# Connector-Section.net
KiCad netlist of a schematic drawn in Altium Designer
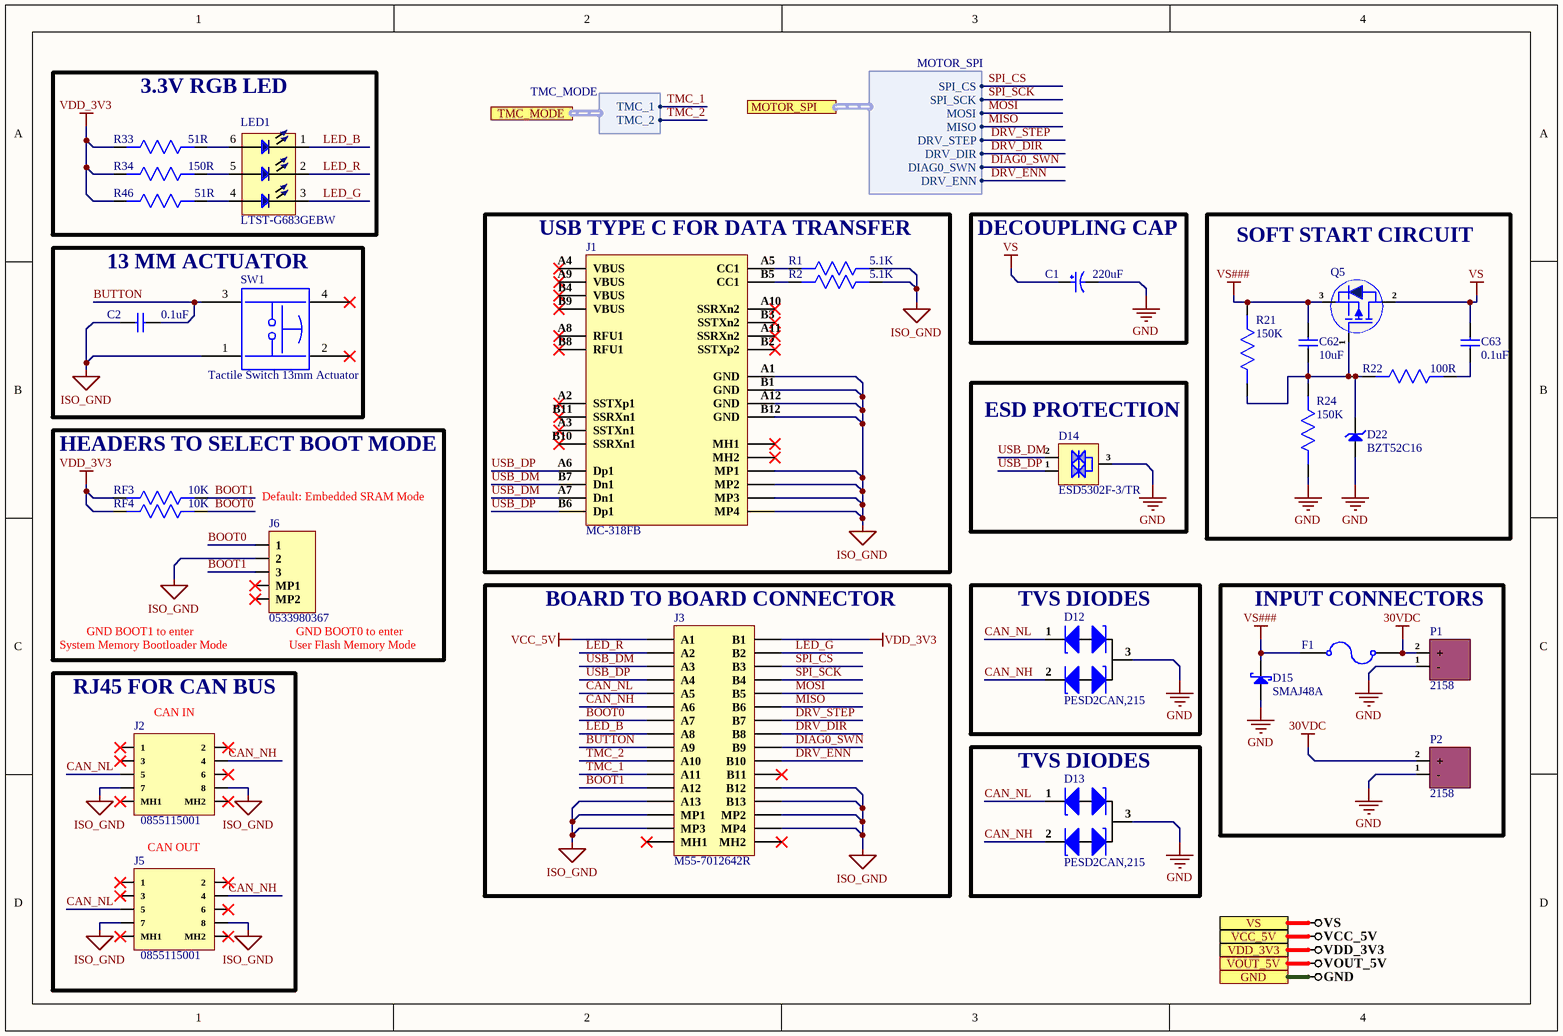
[diagram p0: Connector-Section.SchDoc]

(export (version "E")
  (design (tool "Eeschema 10.0.6"))
  (components
    (comp (ref "C1")
      (value "220uF")
      (footprint "EEEFT1H221AP")
      (description "CAP ALUM 220UF 20% 50V SMD")
      (fields
        (field (name "MANUFACTURER") "Panasonic")
        (field (name "MANUFACTURER PART NUMBER") "EEEFT1H221AP")
      )
      (libsource (lib "eSpark_centralized_Library(2022)") (part "EEEFT1H221AP"))
    )
    (comp (ref "C2")
      (value "0.1uF")
      (footprint "Cap 0603")
      (description "Cap Ceramic 0.1uF 50VDC X7R 10% SMD 0603 Paper T/R")
      (fields
        (field (name "MANUFACTURER") "Samsung")
        (field (name "MANUFACTURER PART NUMBER") "CL10B104KB8NNNC")
      )
      (libsource (lib "Cole_Benson") (part "CL10B104KB8NNNC"))
    )
    (comp (ref "C62")
      (value "10uF")
      (footprint "Cap 0603")
      (description "10uF 35V X5R 20% Pad SMD 0603")
      (fields
        (field (name "MANUFACTURER") "Murata")
        (field (name "MANUFACTURER PART NUMBER") "GRM188R6YA106MA73D")
      )
      (libsource (lib "Cole_Benson") (part "GRM188R6YA106MA73D"))
    )
    (comp (ref "C63")
      (value "0.1uF")
      (footprint "Cap 0603")
      (description "Cap Ceramic 0.1uF 50VDC X7R 10% SMD 0603 Paper T/R")
      (fields
        (field (name "MANUFACTURER") "Samsung")
        (field (name "MANUFACTURER PART NUMBER") "CL10B104KB8NNNC")
      )
      (libsource (lib "Cole_Benson") (part "CL10B104KB8NNNC"))
    )
    (comp (ref "D12")
      (value "PESD2CAN,215")
      (footprint "SOT-23")
      (description "TVS DIODE 24VWM 41VC TO236AB")
      (fields (field (name "MANUFACTURER") "Nexperia"))
      (libsource (lib "Cole_Benson") (part "PESD2CAN,215"))
    )
    (comp (ref "D13")
      (value "PESD2CAN,215")
      (footprint "SOT-23")
      (description "TVS DIODE 24VWM 41VC TO236AB")
      (fields (field (name "MANUFACTURER") "Nexperia"))
      (libsource (lib "Cole_Benson") (part "PESD2CAN,215"))
    )
    (comp (ref "D14")
      (value "ESD5302F-3/TR")
      (footprint "Sot-23")
      (description "16A 20V 7V 5V@Max Unidirectional SOT-23 TVS ROHS")
      (fields (field (name "MANUFACTURER") "WILLSEMI") (field (name "LCSC PART NUMBER") "C239643"))
      (libsource (lib "eSpark Libraries") (part "ESD5302F-3/TR"))
    )
    (comp (ref "D15")
      (value "SMAJ48A")
      (footprint "SMA")
      (description "TVS DIODE 48VWM 77.4VC DO214AC")
      (fields (field (name "MANUFACTURER") "Littelfuse") (field (name "LCSC PART NUMBER") "C223991"))
      (libsource (lib "Cole_Benson") (part "SMAJ48A"))
    )
    (comp (ref "D22")
      (value "BZT52C16")
      (footprint "SOD-123")
      (description "±5% Single 15.3V~17.1V 500mW 16V SOD-123 Zener Diodes ROHS")
      (fields (field (name "MANUFACTURER") "Shikues") (field (name "LCSC PART NUMBER") "C216724"))
      (libsource (lib "Cole_Benson") (part "BZT52C16"))
    )
    (comp (ref "F1")
      (value "0685H9150-01")
      (footprint "0685H9150-01")
      (description "FUSE BOARD MNT 15A 125VAC 32VDC")
      (fields (field (name "MANUFACTURER") "Bel"))
      (libsource (lib "Cole_Benson") (part "0685H9150-01"))
    )
    (comp (ref "J1")
      (value "MC-318FB")
      (footprint "MC-318FB")
      (description "USB 3.0 3A 1 Brick nogging 24 Female -35℃~+75℃ Type-C SMD USB Connectors ROHS")
      (fields (field (name "MANUFACTURER") "SOFNG"))
      (libsource (lib "Cole_Benson") (part "MC-318FB"))
    )
    (comp (ref "J2")
      (value "0855115001")
      (footprint "0855115001")
      (description "CONN MOD JACK 8P8C VERT UNSHLD")
      (fields (field (name "MANUFACTURER") "Molex") (field (name "MANUFACTURER PART NUMBER") "85511-5001"))
      (libsource (lib "eSpark_centralized_Library(2022)") (part "0855115001"))
    )
    (comp (ref "J3")
      (value "M55-7012642R")
      (footprint "M55-7012642R")
      (description "CONN HEADER SMD 26POS 1.27MM")
      (fields (field (name "MANUFACTURER") "Harwin"))
      (libsource (lib "Cole_Benson") (part "M55-7012642R"))
    )
    (comp (ref "J5")
      (value "0855115001")
      (footprint "0855115001")
      (description "CONN MOD JACK 8P8C VERT UNSHLD")
      (fields (field (name "MANUFACTURER") "Molex") (field (name "MANUFACTURER PART NUMBER") "85511-5001"))
      (libsource (lib "eSpark_centralized_Library(2022)") (part "0855115001"))
    )
    (comp (ref "J6")
      (value "0533980367")
      (footprint "0533980367")
      (description "CONN HEADER SMD 3POS 1.25MM")
      (fields (field (name "MANUFACTURER") "Molex"))
      (libsource (lib "Cole_Benson") (part "0533980367"))
    )
    (comp (ref "LED1")
      (value "LTST-G683GEBW")
      (footprint "LTST-G683GEBW")
      (description "Standard LEDs - SMD SMD LED Red/Grn/Blue 625/1550/260 mcd")
      (fields (field (name "MANUFACTURER") "Vishay Lite-On"))
      (libsource (lib "Cole_Benson") (part "LTST-G683GEBW"))
    )
    (comp (ref "P1")
      (value "2158")
      (footprint "2158")
      (description "XT60 Connector Male-Female Pair, Black (Pololu)")
      (fields (field (name "MANUFACTURER") "Polulo"))
      (libsource (lib "Cole_Benson") (part "2158"))
    )
    (comp (ref "P2")
      (value "2158")
      (footprint "2158")
      (description "XT60 Connector Male-Female Pair, Black (Pololu)")
      (fields (field (name "MANUFACTURER") "Polulo"))
      (libsource (lib "Cole_Benson") (part "2158"))
    )
    (comp (ref "Q5")
      (value "STD10P6F6")
      (footprint "DPAK")
      (description "MOSFET P CH 60V 10A DPAK")
      (fields (field (name "MANUFACTURER") "STMicroelectronics") (field (name "LCSC PART NUMBER") "C457501"))
      (libsource (lib "Cole_Benson") (part "STD10P6F6"))
    )
    (comp (ref "R1")
      (value "5.1K")
      (footprint "Res0603")
      (description "RES SMD 5.1K OHM 5% 1/10W 0603")
      (fields
        (field (name "MANUFACTURER") "Yageo")
        (field (name "MANUFACTURER PART NUMBER") "RC0603JR-075K1L")
      )
      (libsource (lib "Cole_Benson") (part "RC0603JR-075K1L"))
    )
    (comp (ref "R2")
      (value "5.1K")
      (footprint "Res0603")
      (description "RES SMD 5.1K OHM 5% 1/10W 0603")
      (fields
        (field (name "MANUFACTURER") "Yageo")
        (field (name "MANUFACTURER PART NUMBER") "RC0603JR-075K1L")
      )
      (libsource (lib "Cole_Benson") (part "RC0603JR-075K1L"))
    )
    (comp (ref "R21")
      (value "150K")
      (footprint "Res0603")
      (description "RES SMD 150K OHM 5% 1/10W 0603")
      (fields
        (field (name "MANUFACTURER") "Yageo")
        (field (name "MANUFACTURER PART NUMBER") "AC0603JR-07150KL")
      )
      (libsource (lib "Cole_Benson") (part "AC0603JR-07150KL"))
    )
    (comp (ref "R22")
      (value "100R")
      (footprint "Res0603")
      (description "RES SMD 100 OHM 1% 1/10W 0603")
      (fields
        (field (name "MANUFACTURER") "Yageo")
        (field (name "MANUFACTURER PART NUMBER") "RC0603FR-07100RL")
      )
      (libsource (lib "Cole_Benson") (part "RC0603FR-07100RL"))
    )
    (comp (ref "R24")
      (value "150K")
      (footprint "Res0603")
      (description "RES SMD 150K OHM 5% 1/10W 0603")
      (fields
        (field (name "MANUFACTURER") "Yageo")
        (field (name "MANUFACTURER PART NUMBER") "AC0603JR-07150KL")
      )
      (libsource (lib "Cole_Benson") (part "AC0603JR-07150KL"))
    )
    (comp (ref "R33")
      (value "51R")
      (footprint "Res0603")
      (description "RES SMD 51R 100mW 0603")
      (fields
        (field (name "MANUFACTURER") "Yageo")
        (field (name "MANUFACTURER PART NUMBER") "RC0603FR-0751RL")
      )
      (libsource (lib "Cole_Benson") (part "RC0603FR-0751RL"))
    )
    (comp (ref "R34")
      (value "150R")
      (footprint "Res0603")
      (description "RES SMD 150OHM 1/10W 0603")
      (fields
        (field (name "MANUFACTURER") "Yageo")
        (field (name "MANUFACTURER PART NUMBER") "RC0603FR-07150RL")
      )
      (libsource (lib "Cole_Benson") (part "RC0603FR-07150RL"))
    )
    (comp (ref "R46")
      (value "51R")
      (footprint "Res0603")
      (description "RES SMD 51R 100mW 0603")
      (fields
        (field (name "MANUFACTURER") "Yageo")
        (field (name "MANUFACTURER PART NUMBER") "RC0603FR-0751RL")
      )
      (libsource (lib "Cole_Benson") (part "RC0603FR-0751RL"))
    )
    (comp (ref "RF3")
      (value "10K")
      (footprint "Res0603")
      (description "RES SMD 10K Ohm 1% 1/10W 0603")
      (fields
        (field (name "MANUFACTURER") "Yageo")
        (field (name "MANUFACTURER PART NUMBER") "RC0603FR-0710KL")
      )
      (libsource (lib "Cole_Benson") (part "RC0603FR-0710KL"))
    )
    (comp (ref "RF4")
      (value "10K")
      (footprint "Res0603")
      (description "RES SMD 10K Ohm 1% 1/10W 0603")
      (fields
        (field (name "MANUFACTURER") "Yageo")
        (field (name "MANUFACTURER PART NUMBER") "RC0603FR-0710KL")
      )
      (libsource (lib "Cole_Benson") (part "RC0603FR-0710KL"))
    )
    (comp (ref "SW1")
      (value "Tactile Switch 13mm Actuator")
      (footprint "Tactile Switch 13mm Actuator")
      (description "Memontary Tactile Push Button Switch 6X6X4.3 / 4.5 / 5/6/7/8/9/10 / 13mm SMD")
      (fields
        (field (name "MANUFACTURER") "WIN ELEC-TECH CO., LTD")
        (field (name "MANUFACTURER PART NO") "Custum")
      )
      (libsource (lib "Cole_Benson") (part "Tactile Switch 13mm Actuator"))
    )
  )
  (nets
    (net (code "3") (name "/BOOT0") (class "Default")
      (node (ref "J3") (pin "A7") (pinfunction "A7_A7") (pintype "passive"))
      (node (ref "J6") (pin "1") (pinfunction "1_1") (pintype "passive"))
      (node (ref "RF4") (pin "1") (pintype "passive"))
    )
    (net (code "4") (name "/BOOT1") (class "Default")
      (node (ref "J3") (pin "A12") (pinfunction "A12_A12") (pintype "passive"))
      (node (ref "J6") (pin "3") (pinfunction "3_3") (pintype "passive"))
      (node (ref "RF3") (pin "1") (pintype "passive"))
    )
    (net (code "5") (name "/BUTTON") (class "Default")
      (node (ref "C2") (pin "2") (pinfunction "2_2") (pintype "passive"))
      (node (ref "J3") (pin "A9") (pinfunction "A9_A9") (pintype "passive"))
      (node (ref "SW1") (pin "3") (pintype "passive"))
    )
    (net (code "6") (name "/CAN_NH") (class "Default")
      (node (ref "D12") (pin "2") (pinfunction "K2_2") (pintype "passive"))
      (node (ref "D13") (pin "2") (pinfunction "K2_2") (pintype "passive"))
      (node (ref "J2") (pin "4") (pinfunction "4_4") (pintype "passive"))
      (node (ref "J3") (pin "A6") (pinfunction "A6_A6") (pintype "passive"))
      (node (ref "J5") (pin "4") (pinfunction "4_4") (pintype "passive"))
    )
    (net (code "7") (name "/CAN_NL") (class "Default")
      (node (ref "D12") (pin "1") (pinfunction "K1_1") (pintype "passive"))
      (node (ref "D13") (pin "1") (pinfunction "K1_1") (pintype "passive"))
      (node (ref "J2") (pin "5") (pinfunction "5_5") (pintype "passive"))
      (node (ref "J3") (pin "A5") (pinfunction "A5_A5") (pintype "passive"))
      (node (ref "J5") (pin "5") (pinfunction "5_5") (pintype "passive"))
    )
    (net (code "8") (name "/DIAG0_SWN") (class "Default")
      (node (ref "J3") (pin "B9") (pinfunction "B9_B9") (pintype "passive"))
    )
    (net (code "9") (name "/DRV_DIR") (class "Default")
      (node (ref "J3") (pin "B8") (pinfunction "B8_B8") (pintype "passive"))
    )
    (net (code "10") (name "/DRV_ENN") (class "Default")
      (node (ref "J3") (pin "B10") (pinfunction "B10_B10") (pintype "passive"))
    )
    (net (code "11") (name "/DRV_STEP") (class "Default")
      (node (ref "J3") (pin "B7") (pinfunction "B7_B7") (pintype "passive"))
    )
    (net (code "12") (name "/LED_B") (class "Default")
      (node (ref "J3") (pin "A8") (pinfunction "A8_A8") (pintype "passive"))
      (node (ref "LED1") (pin "1") (pinfunction "-_1") (pintype "passive"))
    )
    (net (code "13") (name "/LED_G") (class "Default")
      (node (ref "J3") (pin "B2") (pinfunction "B2_B2") (pintype "passive"))
      (node (ref "LED1") (pin "3") (pinfunction "-_3") (pintype "passive"))
    )
    (net (code "14") (name "/LED_R") (class "Default")
      (node (ref "J3") (pin "A2") (pinfunction "A2_A2") (pintype "passive"))
      (node (ref "LED1") (pin "2") (pinfunction "-_2") (pintype "passive"))
    )
    (net (code "15") (name "/MISO") (class "Default")
      (node (ref "J3") (pin "B6") (pinfunction "B6_B6") (pintype "passive"))
    )
    (net (code "16") (name "/MOSI") (class "Default")
      (node (ref "J3") (pin "B5") (pinfunction "B5_B5") (pintype "passive"))
    )
    (net (code "17") (name "/SPI_CS") (class "Default")
      (node (ref "J3") (pin "B3") (pinfunction "B3_B3") (pintype "passive"))
    )
    (net (code "18") (name "/SPI_SCK") (class "Default")
      (node (ref "J3") (pin "B4") (pinfunction "B4_B4") (pintype "passive"))
    )
    (net (code "19") (name "/TMC_1") (class "Default")
      (node (ref "J3") (pin "A11") (pinfunction "A11_A11") (pintype "passive"))
    )
    (net (code "20") (name "/TMC_2") (class "Default")
      (node (ref "J3") (pin "A10") (pinfunction "A10_A10") (pintype "passive"))
    )
    (net (code "21") (name "/USB_DM") (class "Default")
      (node (ref "D14") (pin "2") (pinfunction "I/O2_2") (pintype "passive"))
      (node (ref "J1") (pin "A7") (pinfunction "Dn1_A7") (pintype "passive"))
      (node (ref "J1") (pin "B7") (pinfunction "Dn1_B7") (pintype "passive"))
      (node (ref "J3") (pin "A3") (pinfunction "A3_A3") (pintype "passive"))
    )
    (net (code "22") (name "/USB_DP") (class "Default")
      (node (ref "D14") (pin "1") (pinfunction "I/O1_1") (pintype "passive"))
      (node (ref "J1") (pin "A6") (pinfunction "Dp1_A6") (pintype "passive"))
      (node (ref "J1") (pin "B6") (pinfunction "Dp1_B6") (pintype "passive"))
      (node (ref "J3") (pin "A4") (pinfunction "A4_A4") (pintype "passive"))
    )
    (net (code "25") (name "30VDC") (class "Default")
      (node (ref "F1") (pin "2") (pinfunction "2_2") (pintype "passive"))
      (node (ref "P1") (pin "2") (pinfunction "+_2") (pintype "passive"))
      (node (ref "P2") (pin "2") (pinfunction "+_2") (pintype "passive"))
    )
    (net (code "26") (name "GND") (class "Default")
      (node (ref "C1") (pin "2") (pintype "passive"))
      (node (ref "D12") (pin "3") (pinfunction "C_K_3") (pintype "passive"))
      (node (ref "D13") (pin "3") (pinfunction "C_K_3") (pintype "passive"))
      (node (ref "D14") (pin "3") (pinfunction "GND_3") (pintype "passive"))
      (node (ref "D15") (pin "2") (pinfunction "A_2") (pintype "passive"))
      (node (ref "D22") (pin "1") (pinfunction "A_1") (pintype "passive"))
      (node (ref "P1") (pin "1") (pinfunction "-_1") (pintype "passive"))
      (node (ref "P2") (pin "1") (pinfunction "-_1") (pintype "passive"))
      (node (ref "R24") (pin "2") (pintype "passive"))
    )
    (net (code "27") (name "ISO_GND") (class "Default")
      (node (ref "C2") (pin "1") (pinfunction "1_1") (pintype "passive"))
      (node (ref "J1") (pin "A1") (pinfunction "GND_A1") (pintype "passive"))
      (node (ref "J1") (pin "A12") (pinfunction "GND_A12") (pintype "passive"))
      (node (ref "J1") (pin "B1") (pinfunction "GND_B1") (pintype "passive"))
      (node (ref "J1") (pin "B12") (pinfunction "GND_B12") (pintype "passive"))
      (node (ref "J1") (pin "MP1") (pinfunction "MP1_MP1") (pintype "passive"))
      (node (ref "J1") (pin "MP2") (pinfunction "MP2_MP2") (pintype "passive"))
      (node (ref "J1") (pin "MP3") (pinfunction "MP3_MP3") (pintype "passive"))
      (node (ref "J1") (pin "MP4") (pinfunction "MP4_MP4") (pintype "passive"))
      (node (ref "J2") (pin "7") (pinfunction "7_7") (pintype "passive"))
      (node (ref "J2") (pin "8") (pinfunction "8_8") (pintype "passive"))
      (node (ref "J3") (pin "A13") (pinfunction "A13_A13") (pintype "passive"))
      (node (ref "J3") (pin "B12") (pinfunction "B12_B12") (pintype "passive"))
      (node (ref "J3") (pin "B13") (pinfunction "B13_B13") (pintype "passive"))
      (node (ref "J3") (pin "MP1") (pinfunction "MP1_MP1") (pintype "passive"))
      (node (ref "J3") (pin "MP2") (pinfunction "MP2_MP2") (pintype "passive"))
      (node (ref "J3") (pin "MP3") (pinfunction "MP3_MP3") (pintype "passive"))
      (node (ref "J3") (pin "MP4") (pinfunction "MP4_MP4") (pintype "passive"))
      (node (ref "J5") (pin "7") (pinfunction "7_7") (pintype "passive"))
      (node (ref "J5") (pin "8") (pinfunction "8_8") (pintype "passive"))
      (node (ref "J6") (pin "2") (pinfunction "2_2") (pintype "passive"))
      (node (ref "R1") (pin "1") (pintype "passive"))
      (node (ref "R2") (pin "1") (pintype "passive"))
      (node (ref "SW1") (pin "1") (pintype "passive"))
    )
    (net (code "28") (name "Net-(C63-Pad1)") (class "Default")
      (node (ref "C63") (pin "1") (pinfunction "1_1") (pintype "passive"))
      (node (ref "R22") (pin "1") (pintype "passive"))
    )
    (net (code "29") (name "Net-(D22-K)") (class "Default")
      (node (ref "C62") (pin "1") (pinfunction "1_1") (pintype "passive"))
      (node (ref "D22") (pin "2") (pinfunction "K_2") (pintype "passive"))
      (node (ref "Q5") (pin "1") (pinfunction "G_1") (pintype "passive"))
      (node (ref "R21") (pin "2") (pintype "passive"))
      (node (ref "R22") (pin "2") (pintype "passive"))
      (node (ref "R24") (pin "1") (pintype "passive"))
    )
    (net (code "30") (name "Net-(J1-CC1-PadA5)") (class "Default")
      (node (ref "J1") (pin "A5") (pinfunction "CC1_A5") (pintype "passive"))
      (node (ref "R1") (pin "2") (pintype "passive"))
    )
    (net (code "31") (name "Net-(J1-CC1-PadB5)") (class "Default")
      (node (ref "J1") (pin "B5") (pinfunction "CC1_B5") (pintype "passive"))
      (node (ref "R2") (pin "2") (pintype "passive"))
    )
    (net (code "32") (name "Net-(LED1-+-Pad4)") (class "Default")
      (node (ref "LED1") (pin "4") (pinfunction "+_4") (pintype "passive"))
      (node (ref "R46") (pin "1") (pintype "passive"))
    )
    (net (code "33") (name "Net-(LED1-+-Pad5)") (class "Default")
      (node (ref "LED1") (pin "5") (pinfunction "+_5") (pintype "passive"))
      (node (ref "R34") (pin "1") (pintype "passive"))
    )
    (net (code "34") (name "Net-(LED1-+-Pad6)") (class "Default")
      (node (ref "LED1") (pin "6") (pinfunction "+_6") (pintype "passive"))
      (node (ref "R33") (pin "1") (pintype "passive"))
    )
    (net (code "35") (name "VCC_5V") (class "Default")
      (node (ref "J3") (pin "A1") (pinfunction "A1_A1") (pintype "passive"))
    )
    (net (code "36") (name "VDD_3V3") (class "Default")
      (node (ref "J3") (pin "B1") (pinfunction "B1_B1") (pintype "passive"))
      (node (ref "R33") (pin "2") (pintype "passive"))
      (node (ref "R34") (pin "2") (pintype "passive"))
      (node (ref "R46") (pin "2") (pintype "passive"))
      (node (ref "RF3") (pin "2") (pintype "passive"))
      (node (ref "RF4") (pin "2") (pintype "passive"))
    )
    (net (code "38") (name "VS") (class "Default")
      (node (ref "C1") (pin "1") (pintype "passive"))
      (node (ref "C63") (pin "2") (pinfunction "2_2") (pintype "passive"))
      (node (ref "Q5") (pin "2") (pinfunction "D_2") (pintype "passive"))
    )
    (net (code "39") (name "VS###") (class "Default")
      (node (ref "C62") (pin "2") (pinfunction "2_2") (pintype "passive"))
      (node (ref "D15") (pin "1") (pinfunction "K_1") (pintype "passive"))
      (node (ref "F1") (pin "1") (pinfunction "1_1") (pintype "passive"))
      (node (ref "Q5") (pin "3") (pinfunction "S_3") (pintype "passive"))
      (node (ref "R21") (pin "1") (pintype "passive"))
    )
    (net (code "40") (name "unconnected-(J1-PadMH1)") (class "Default")
      (node (ref "J1") (pin "MH1") (pinfunction "MH1_MH1") (pintype "passive+no_connect"))
    )
    (net (code "41") (name "unconnected-(J1-PadMH2)") (class "Default")
      (node (ref "J1") (pin "MH2") (pinfunction "MH2_MH2") (pintype "passive+no_connect"))
    )
    (net (code "42") (name "unconnected-(J1-RFU1-PadA8)") (class "Default")
      (node (ref "J1") (pin "A8") (pinfunction "RFU1_A8") (pintype "passive+no_connect"))
    )
    (net (code "43") (name "unconnected-(J1-RFU1-PadB8)") (class "Default")
      (node (ref "J1") (pin "B8") (pinfunction "RFU1_B8") (pintype "passive+no_connect"))
    )
    (net (code "44") (name "unconnected-(J1-SSRXn1-PadB10)") (class "Default")
      (node (ref "J1") (pin "B10") (pinfunction "SSRXn1_B10") (pintype "passive+no_connect"))
    )
    (net (code "45") (name "unconnected-(J1-SSRXn1-PadB11)") (class "Default")
      (node (ref "J1") (pin "B11") (pinfunction "SSRXn1_B11") (pintype "passive+no_connect"))
    )
    (net (code "46") (name "unconnected-(J1-SSRXn2-PadA10)") (class "Default")
      (node (ref "J1") (pin "A10") (pinfunction "SSRXn2_A10") (pintype "passive+no_connect"))
    )
    (net (code "47") (name "unconnected-(J1-SSRXn2-PadA11)") (class "Default")
      (node (ref "J1") (pin "A11") (pinfunction "SSRXn2_A11") (pintype "passive+no_connect"))
    )
    (net (code "48") (name "unconnected-(J1-SSTXn1-PadA3)") (class "Default")
      (node (ref "J1") (pin "A3") (pinfunction "SSTXn1_A3") (pintype "passive+no_connect"))
    )
    (net (code "49") (name "unconnected-(J1-SSTXn2-PadB3)") (class "Default")
      (node (ref "J1") (pin "B3") (pinfunction "SSTXn2_B3") (pintype "passive+no_connect"))
    )
    (net (code "50") (name "unconnected-(J1-SSTXp1-PadA2)") (class "Default")
      (node (ref "J1") (pin "A2") (pinfunction "SSTXp1_A2") (pintype "passive+no_connect"))
    )
    (net (code "51") (name "unconnected-(J1-SSTXp2-PadB2)") (class "Default")
      (node (ref "J1") (pin "B2") (pinfunction "SSTXp2_B2") (pintype "passive+no_connect"))
    )
    (net (code "52") (name "unconnected-(J1-VBUS-PadA4)") (class "Default")
      (node (ref "J1") (pin "A4") (pinfunction "VBUS_A4") (pintype "passive+no_connect"))
    )
    (net (code "53") (name "unconnected-(J1-VBUS-PadA9)") (class "Default")
      (node (ref "J1") (pin "A9") (pinfunction "VBUS_A9") (pintype "passive+no_connect"))
    )
    (net (code "54") (name "unconnected-(J1-VBUS-PadB4)") (class "Default")
      (node (ref "J1") (pin "B4") (pinfunction "VBUS_B4") (pintype "passive+no_connect"))
    )
    (net (code "55") (name "unconnected-(J1-VBUS-PadB9)") (class "Default")
      (node (ref "J1") (pin "B9") (pinfunction "VBUS_B9") (pintype "passive+no_connect"))
    )
    (net (code "56") (name "unconnected-(J2-Pad1)") (class "Default")
      (node (ref "J2") (pin "1") (pinfunction "1_1") (pintype "passive+no_connect"))
    )
    (net (code "57") (name "unconnected-(J2-Pad2)") (class "Default")
      (node (ref "J2") (pin "2") (pinfunction "2_2") (pintype "passive+no_connect"))
    )
    (net (code "58") (name "unconnected-(J2-Pad3)") (class "Default")
      (node (ref "J2") (pin "3") (pinfunction "3_3") (pintype "passive+no_connect"))
    )
    (net (code "59") (name "unconnected-(J2-Pad6)") (class "Default")
      (node (ref "J2") (pin "6") (pinfunction "6_6") (pintype "passive+no_connect"))
    )
    (net (code "60") (name "unconnected-(J2-PadMH1)") (class "Default")
      (node (ref "J2") (pin "MH1") (pinfunction "MH1_MH1") (pintype "passive+no_connect"))
    )
    (net (code "61") (name "unconnected-(J2-PadMH2)") (class "Default")
      (node (ref "J2") (pin "MH2") (pinfunction "MH2_MH2") (pintype "passive+no_connect"))
    )
    (net (code "62") (name "unconnected-(J3-PadB11)") (class "Default")
      (node (ref "J3") (pin "B11") (pinfunction "B11_B11") (pintype "passive+no_connect"))
    )
    (net (code "63") (name "unconnected-(J3-PadMH1)") (class "Default")
      (node (ref "J3") (pin "MH1") (pinfunction "MH1_MH1") (pintype "passive+no_connect"))
    )
    (net (code "64") (name "unconnected-(J3-PadMH2)") (class "Default")
      (node (ref "J3") (pin "MH2") (pinfunction "MH2_MH2") (pintype "passive+no_connect"))
    )
    (net (code "65") (name "unconnected-(J5-Pad1)") (class "Default")
      (node (ref "J5") (pin "1") (pinfunction "1_1") (pintype "passive+no_connect"))
    )
    (net (code "66") (name "unconnected-(J5-Pad2)") (class "Default")
      (node (ref "J5") (pin "2") (pinfunction "2_2") (pintype "passive+no_connect"))
    )
    (net (code "67") (name "unconnected-(J5-Pad3)") (class "Default")
      (node (ref "J5") (pin "3") (pinfunction "3_3") (pintype "passive+no_connect"))
    )
    (net (code "68") (name "unconnected-(J5-Pad6)") (class "Default")
      (node (ref "J5") (pin "6") (pinfunction "6_6") (pintype "passive+no_connect"))
    )
    (net (code "69") (name "unconnected-(J5-PadMH1)") (class "Default")
      (node (ref "J5") (pin "MH1") (pinfunction "MH1_MH1") (pintype "passive+no_connect"))
    )
    (net (code "70") (name "unconnected-(J5-PadMH2)") (class "Default")
      (node (ref "J5") (pin "MH2") (pinfunction "MH2_MH2") (pintype "passive+no_connect"))
    )
    (net (code "71") (name "unconnected-(J6-PadMP1)") (class "Default")
      (node (ref "J6") (pin "MP1") (pinfunction "MP1_MP1") (pintype "passive+no_connect"))
    )
    (net (code "72") (name "unconnected-(J6-PadMP2)") (class "Default")
      (node (ref "J6") (pin "MP2") (pinfunction "MP2_MP2") (pintype "passive+no_connect"))
    )
    (net (code "73") (name "unconnected-(SW1-Pad2)") (class "Default")
      (node (ref "SW1") (pin "2") (pintype "passive+no_connect"))
    )
    (net (code "74") (name "unconnected-(SW1-Pad4)") (class "Default")
      (node (ref "SW1") (pin "4") (pintype "passive+no_connect"))
    )
  )
)
